# MINI_SSTC.net
KiCad netlist of a schematic drawn in EAGLE
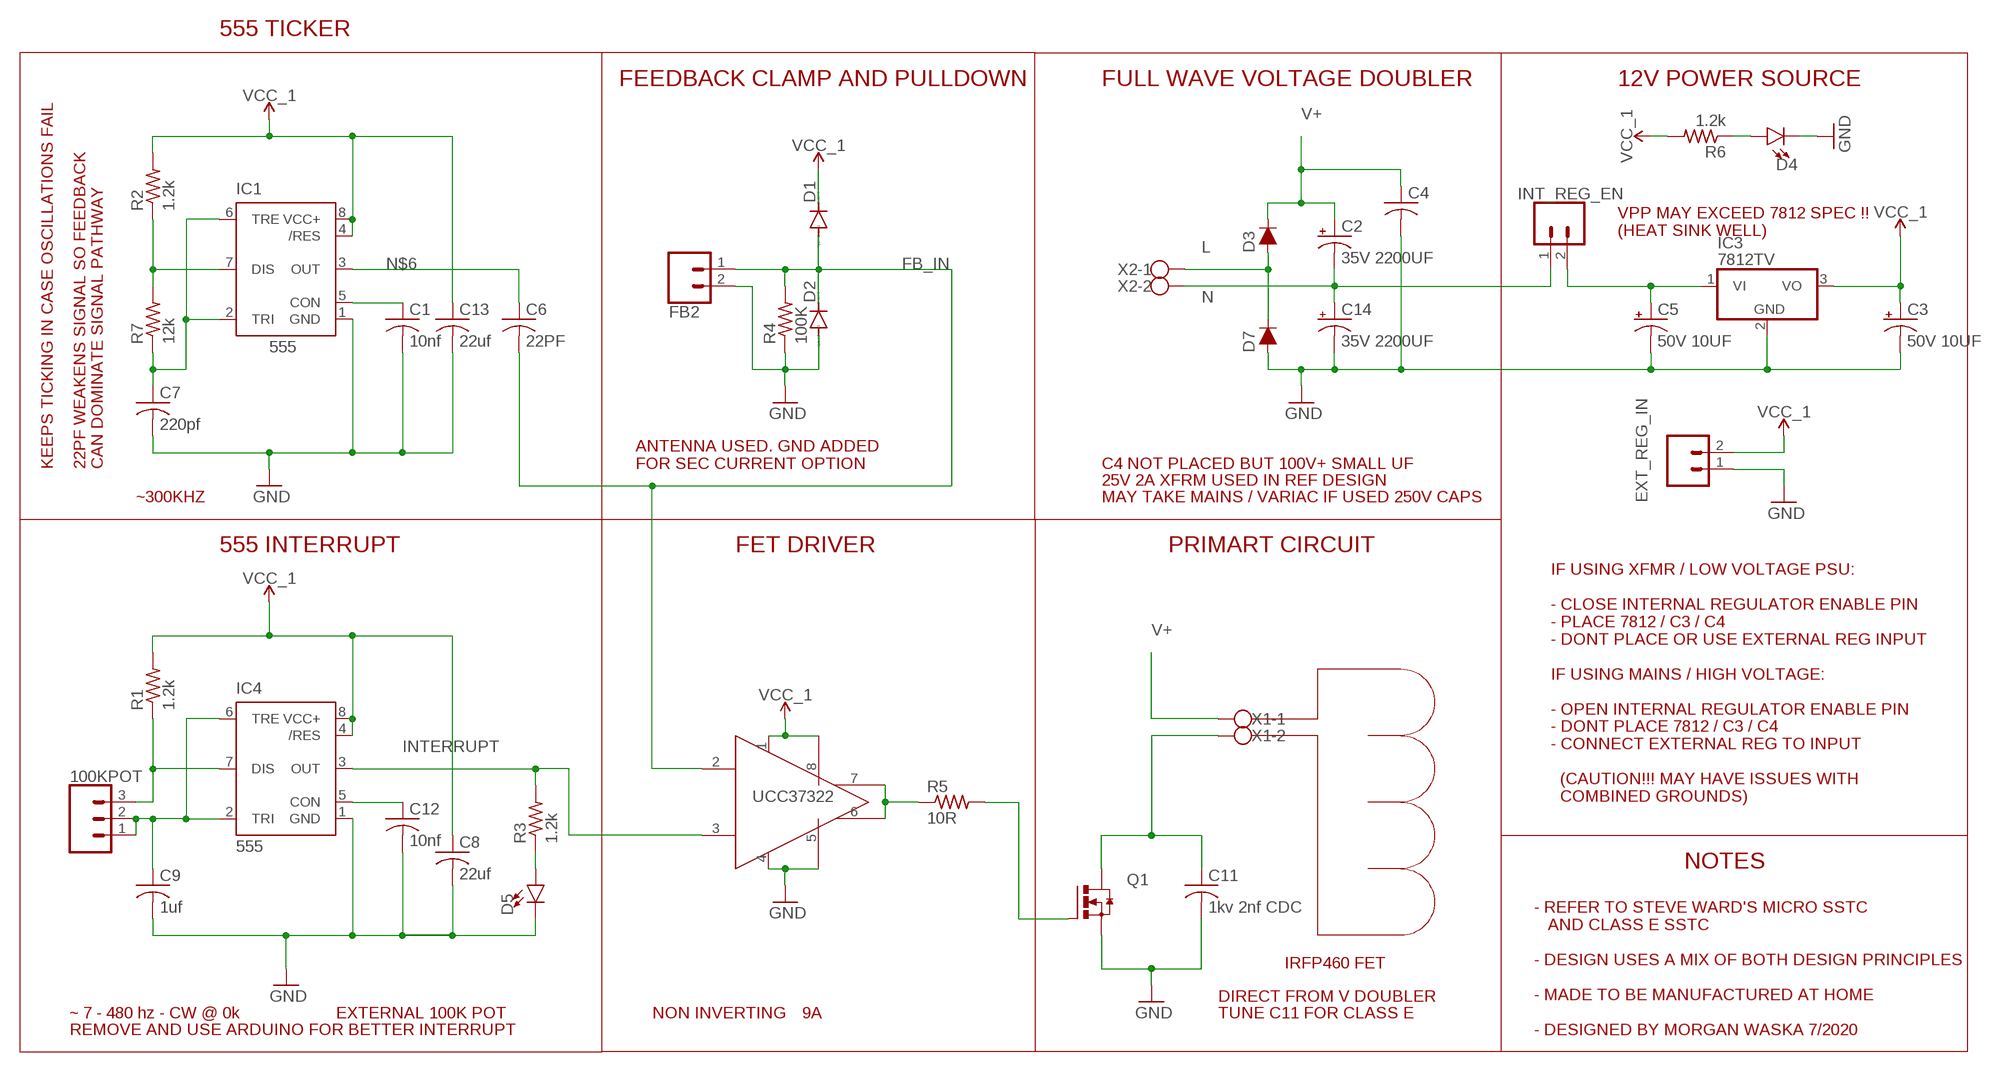
[diagram p0: schematic, sheet 1]

(export (version "E")
  (design (tool "Eeschema 10.0.6"))
  (components
    (comp (ref "100KPOT")
      (value "455-1750-1-ND")
      (footprint "eagle-import:1X03")
      (libsource (lib "eagle-import") (part "CONN_03"))
    )
    (comp (ref "C1")
      (value "10nf")
      (footprint "eagle-import:C025-040X050")
      (libsource (lib "eagle-import") (part "C-US025-040X050"))
    )
    (comp (ref "C2")
      (value "35V 2200UF")
      (footprint "eagle-import:E7,5-18")
      (libsource (lib "eagle-import") (part "CPOL-USE7.5-18"))
    )
    (comp (ref "C3")
      (value "50V 10UF")
      (footprint "eagle-import:E2,5-5")
      (libsource (lib "eagle-import") (part "CPOL-USE2.5-5"))
    )
    (comp (ref "C4")
      (value "C-US025-040X050")
      (footprint "eagle-import:C025-040X050")
      (libsource (lib "eagle-import") (part "C-US025-040X050"))
    )
    (comp (ref "C5")
      (value "50V 10UF")
      (footprint "eagle-import:E2,5-5")
      (libsource (lib "eagle-import") (part "CPOL-USE2.5-5"))
    )
    (comp (ref "C6")
      (value "22PF")
      (footprint "eagle-import:C025-040X050")
      (libsource (lib "eagle-import") (part "C-US025-040X050"))
    )
    (comp (ref "C7")
      (value "220pf")
      (footprint "eagle-import:C025-040X050")
      (libsource (lib "eagle-import") (part "C-US025-040X050"))
    )
    (comp (ref "C8")
      (value "22uf")
      (footprint "eagle-import:C025-040X050")
      (libsource (lib "eagle-import") (part "C-US025-040X050"))
    )
    (comp (ref "C9")
      (value "1uf")
      (footprint "eagle-import:C025-040X050")
      (libsource (lib "eagle-import") (part "C-US025-040X050"))
    )
    (comp (ref "C11")
      (value "1kv 2nf CDC")
      (footprint "eagle-import:C150-054X183")
      (libsource (lib "eagle-import") (part "C-US150-054X183"))
    )
    (comp (ref "C12")
      (value "10nf")
      (footprint "eagle-import:C025-040X050")
      (libsource (lib "eagle-import") (part "C-US025-040X050"))
    )
    (comp (ref "C13")
      (value "22uf")
      (footprint "eagle-import:C025-040X050")
      (libsource (lib "eagle-import") (part "C-US025-040X050"))
    )
    (comp (ref "C14")
      (value "35V 2200UF")
      (footprint "eagle-import:E7,5-18")
      (libsource (lib "eagle-import") (part "CPOL-USE7.5-18"))
    )
    (comp (ref "D1")
      (value "1N4148DO35-7")
      (footprint "eagle-import:DO35-7")
      (libsource (lib "eagle-import") (part "1N4148DO35-7"))
    )
    (comp (ref "D2")
      (value "1N4148DO35-7")
      (footprint "eagle-import:DO35-7")
      (libsource (lib "eagle-import") (part "1N4148DO35-7"))
    )
    (comp (ref "D3")
      (value "MUR460")
      (footprint "eagle-import:DIODE-1N4001-KIT")
      (libsource (lib "eagle-import") (part "DIODE-KIT2"))
    )
    (comp (ref "D4")
      (value "LED5MM")
      (footprint "eagle-import:LED_5MM")
      (libsource (lib "eagle-import") (part "LED5MM"))
    )
    (comp (ref "D5")
      (value "LED5MM")
      (footprint "eagle-import:LED_5MM")
      (libsource (lib "eagle-import") (part "LED5MM"))
    )
    (comp (ref "D7")
      (value "MUR460")
      (footprint "eagle-import:DIODE-1N4001-KIT")
      (libsource (lib "eagle-import") (part "DIODE-KIT2"))
    )
    (comp (ref "EXT_REG_IN")
      (value "CONN_02")
      (footprint "eagle-import:1X02")
      (libsource (lib "eagle-import") (part "CONN_02"))
    )
    (comp (ref "FB2")
      (value "CONN_02")
      (footprint "eagle-import:1X02")
      (libsource (lib "eagle-import") (part "CONN_02"))
    )
    (comp (ref "IC1")
      (value "555")
      (footprint "eagle-import:DIP08-KIT")
      (libsource (lib "eagle-import") (part "555KIT"))
    )
    (comp (ref "IC2")
      (value "UCC37322")
      (footprint "eagle-import:DIL08")
      (libsource (lib "eagle-import") (part "UCC37321DIL8"))
    )
    (comp (ref "IC3")
      (value "7812TV")
      (footprint "eagle-import:TO220V")
      (libsource (lib "eagle-import") (part "78TV12"))
    )
    (comp (ref "IC4")
      (value "555")
      (footprint "eagle-import:DIP08-KIT")
      (libsource (lib "eagle-import") (part "555KIT"))
    )
    (comp (ref "INT_REG_EN")
      (value "CONN_02")
      (footprint "eagle-import:1X02")
      (libsource (lib "eagle-import") (part "CONN_02"))
    )
    (comp (ref "Q1")
      (value "IRFP460")
      (footprint "eagle-import:TO247BV")
      (libsource (lib "eagle-import") (part "IRFP240"))
    )
    (comp (ref "R1")
      (value "1.2k")
      (footprint "eagle-import:0207_9")
      (libsource (lib "eagle-import") (part "R-US_0207/9"))
    )
    (comp (ref "R2")
      (value "1.2k")
      (footprint "eagle-import:0207_9")
      (libsource (lib "eagle-import") (part "R-US_0207/9"))
    )
    (comp (ref "R3")
      (value "1.2k")
      (footprint "eagle-import:0207_9")
      (libsource (lib "eagle-import") (part "R-US_0207/9"))
    )
    (comp (ref "R4")
      (value "100K")
      (footprint "eagle-import:0207_9")
      (libsource (lib "eagle-import") (part "R-US_0207/9"))
    )
    (comp (ref "R5")
      (value "10R")
      (footprint "eagle-import:0207_9")
      (libsource (lib "eagle-import") (part "R-US_0207/9"))
    )
    (comp (ref "R6")
      (value "1.2k")
      (footprint "eagle-import:0207_9")
      (libsource (lib "eagle-import") (part "R-US_0207/9"))
    )
    (comp (ref "R7")
      (value "12k")
      (footprint "eagle-import:0207_9")
      (libsource (lib "eagle-import") (part "R-US_0207/9"))
    )
    (comp (ref "X1")
      (value "W237-102")
      (footprint "eagle-import:W237-102")
      (fields (field (name "MPN") "237-102"))
      (libsource (lib "eagle-import") (part "W237-102"))
    )
    (comp (ref "X2")
      (value "W237-102")
      (footprint "eagle-import:W237-102")
      (fields (field (name "MPN") "237-102"))
      (libsource (lib "eagle-import") (part "W237-102"))
    )
  )
  (nets
    (net (code "1") (name "/FB_IN") (class "Default")
      (node (ref "C6") (pin "2") (pinfunction "2_2") (pintype "passive"))
      (node (ref "D1") (pin "A") (pinfunction "A_A") (pintype "passive"))
      (node (ref "D2") (pin "C") (pinfunction "C_C") (pintype "passive"))
      (node (ref "FB2") (pin "1") (pinfunction "1_1") (pintype "passive"))
      (node (ref "IC2") (pin "2") (pinfunction "2_IN_2") (pintype "input"))
      (node (ref "R4") (pin "2") (pinfunction "2_2") (pintype "passive"))
    )
    (net (code "2") (name "/INTERRUPT") (class "Default")
      (node (ref "IC2") (pin "3") (pinfunction "3_ENBL_3") (pintype "input"))
      (node (ref "IC4") (pin "3") (pinfunction "OUT_3") (pintype "output"))
      (node (ref "R3") (pin "2") (pinfunction "2_2") (pintype "passive"))
    )
    (net (code "3") (name "/L") (class "Default")
      (node (ref "D3") (pin "A") (pinfunction "A_A") (pintype "passive"))
      (node (ref "D7") (pin "C") (pinfunction "C_C") (pintype "passive"))
      (node (ref "X2") (pin "1") (pinfunction "KL_1") (pintype "passive"))
    )
    (net (code "4") (name "/N") (class "Default")
      (node (ref "C14") (pin "+") (pinfunction "+_+") (pintype "passive"))
      (node (ref "C2") (pin "-") (pinfunction "-_-") (pintype "passive"))
      (node (ref "INT_REG_EN") (pin "1") (pinfunction "1_1") (pintype "passive"))
      (node (ref "X2") (pin "2") (pinfunction "KL_2") (pintype "passive"))
    )
    (net (code "5") (name "/N$6") (class "Default")
      (node (ref "C6") (pin "1") (pinfunction "1_1") (pintype "passive"))
      (node (ref "IC1") (pin "3") (pinfunction "OUT_3") (pintype "output"))
    )
    (net (code "6") (name "/V+") (class "Default")
      (node (ref "C2") (pin "+") (pinfunction "+_+") (pintype "passive"))
      (node (ref "C4") (pin "1") (pinfunction "1_1") (pintype "passive"))
      (node (ref "D3") (pin "C") (pinfunction "C_C") (pintype "passive"))
      (node (ref "X1") (pin "1") (pinfunction "KL_1") (pintype "passive"))
    )
    (net (code "7") (name "GND") (class "Default")
      (node (ref "C1") (pin "2") (pinfunction "2_2") (pintype "passive"))
      (node (ref "C11") (pin "2") (pinfunction "2_2") (pintype "passive"))
      (node (ref "C12") (pin "2") (pinfunction "2_2") (pintype "passive"))
      (node (ref "C13") (pin "2") (pinfunction "2_2") (pintype "passive"))
      (node (ref "C14") (pin "-") (pinfunction "-_-") (pintype "passive"))
      (node (ref "C3") (pin "-") (pinfunction "-_-") (pintype "passive"))
      (node (ref "C4") (pin "2") (pinfunction "2_2") (pintype "passive"))
      (node (ref "C5") (pin "-") (pinfunction "-_-") (pintype "passive"))
      (node (ref "C7") (pin "2") (pinfunction "2_2") (pintype "passive"))
      (node (ref "C8") (pin "2") (pinfunction "2_2") (pintype "passive"))
      (node (ref "C9") (pin "2") (pinfunction "2_2") (pintype "passive"))
      (node (ref "D2") (pin "A") (pinfunction "A_A") (pintype "passive"))
      (node (ref "D4") (pin "K") (pinfunction "C_K") (pintype "passive"))
      (node (ref "D5") (pin "K") (pinfunction "C_K") (pintype "passive"))
      (node (ref "D7") (pin "A") (pinfunction "A_A") (pintype "passive"))
      (node (ref "EXT_REG_IN") (pin "1") (pinfunction "1_1") (pintype "passive"))
      (node (ref "FB2") (pin "2") (pinfunction "2_2") (pintype "passive"))
      (node (ref "IC1") (pin "1") (pinfunction "GND_1") (pintype "power_in"))
      (node (ref "IC2") (pin "4") (pinfunction "4_AGND_4") (pintype "power_in"))
      (node (ref "IC2") (pin "5") (pinfunction "5_PGND_5") (pintype "power_in"))
      (node (ref "IC3") (pin "2") (pinfunction "GND_2") (pintype "passive"))
      (node (ref "IC4") (pin "1") (pinfunction "GND_1") (pintype "power_in"))
      (node (ref "Q1") (pin "S") (pinfunction "S_S") (pintype "passive"))
      (node (ref "R4") (pin "1") (pinfunction "1_1") (pintype "passive"))
    )
    (net (code "8") (name "Net-(D4-PadA)") (class "Default")
      (node (ref "D4") (pin "A") (pinfunction "A_A") (pintype "passive"))
      (node (ref "R6") (pin "1") (pinfunction "1_1") (pintype "passive"))
    )
    (net (code "9") (name "Net-(D5-PadA)") (class "Default")
      (node (ref "D5") (pin "A") (pinfunction "A_A") (pintype "passive"))
      (node (ref "R3") (pin "1") (pinfunction "1_1") (pintype "passive"))
    )
    (net (code "10") (name "Net-(IC1-CON)") (class "Default")
      (node (ref "C1") (pin "1") (pinfunction "1_1") (pintype "passive"))
      (node (ref "IC1") (pin "5") (pinfunction "CON_5") (pintype "input"))
    )
    (net (code "11") (name "Net-(IC1-DIS)") (class "Default")
      (node (ref "IC1") (pin "7") (pinfunction "DIS_7") (pintype "input"))
      (node (ref "R2") (pin "1") (pinfunction "1_1") (pintype "passive"))
      (node (ref "R7") (pin "2") (pinfunction "2_2") (pintype "passive"))
    )
    (net (code "12") (name "Net-(IC1-TRE)") (class "Default")
      (node (ref "C7") (pin "1") (pinfunction "1_1") (pintype "passive"))
      (node (ref "IC1") (pin "2") (pinfunction "TRI_2") (pintype "input"))
      (node (ref "IC1") (pin "6") (pinfunction "TRE_6") (pintype "input"))
      (node (ref "R7") (pin "1") (pinfunction "1_1") (pintype "passive"))
    )
    (net (code "13") (name "Net-(IC2-6_OUT)") (class "Default")
      (node (ref "IC2") (pin "6") (pinfunction "6_OUT_6") (pintype "output"))
      (node (ref "IC2") (pin "7") (pinfunction "7_OUT_7") (pintype "output"))
      (node (ref "R5") (pin "1") (pinfunction "1_1") (pintype "passive"))
    )
    (net (code "14") (name "Net-(IC3-VI)") (class "Default")
      (node (ref "C5") (pin "+") (pinfunction "+_+") (pintype "passive"))
      (node (ref "IC3") (pin "1") (pinfunction "VI_1") (pintype "input"))
      (node (ref "INT_REG_EN") (pin "2") (pinfunction "2_2") (pintype "passive"))
    )
    (net (code "15") (name "Net-(IC4-CON)") (class "Default")
      (node (ref "C12") (pin "1") (pinfunction "1_1") (pintype "passive"))
      (node (ref "IC4") (pin "5") (pinfunction "CON_5") (pintype "input"))
    )
    (net (code "16") (name "Net-(IC4-DIS)") (class "Default")
      (node (ref "100KPOT") (pin "3") (pinfunction "3_3") (pintype "passive"))
      (node (ref "IC4") (pin "7") (pinfunction "DIS_7") (pintype "input"))
      (node (ref "R1") (pin "1") (pinfunction "1_1") (pintype "passive"))
    )
    (net (code "17") (name "Net-(IC4-TRE)") (class "Default")
      (node (ref "100KPOT") (pin "1") (pinfunction "1_1") (pintype "passive"))
      (node (ref "100KPOT") (pin "2") (pinfunction "2_2") (pintype "passive"))
      (node (ref "C9") (pin "1") (pinfunction "1_1") (pintype "passive"))
      (node (ref "IC4") (pin "2") (pinfunction "TRI_2") (pintype "input"))
      (node (ref "IC4") (pin "6") (pinfunction "TRE_6") (pintype "input"))
    )
    (net (code "18") (name "Net-(Q1-PadG)") (class "Default")
      (node (ref "Q1") (pin "G") (pinfunction "G_G") (pintype "passive"))
      (node (ref "R5") (pin "2") (pinfunction "2_2") (pintype "passive"))
    )
    (net (code "19") (name "Net-(X1B-KL)") (class "Default")
      (node (ref "C11") (pin "1") (pinfunction "1_1") (pintype "passive"))
      (node (ref "Q1") (pin "D") (pinfunction "D_D") (pintype "passive"))
      (node (ref "X1") (pin "2") (pinfunction "KL_2") (pintype "passive"))
    )
    (net (code "20") (name "VCC_1") (class "Default")
      (node (ref "C13") (pin "1") (pinfunction "1_1") (pintype "passive"))
      (node (ref "C3") (pin "+") (pinfunction "+_+") (pintype "passive"))
      (node (ref "C8") (pin "1") (pinfunction "1_1") (pintype "passive"))
      (node (ref "D1") (pin "C") (pinfunction "C_C") (pintype "passive"))
      (node (ref "EXT_REG_IN") (pin "2") (pinfunction "2_2") (pintype "passive"))
      (node (ref "IC1") (pin "4") (pinfunction "/RES_4") (pintype "input"))
      (node (ref "IC1") (pin "8") (pinfunction "VCC+_8") (pintype "power_in"))
      (node (ref "IC2") (pin "1") (pinfunction "1_VDD_1") (pintype "power_in"))
      (node (ref "IC2") (pin "8") (pinfunction "8_VDD_8") (pintype "power_in"))
      (node (ref "IC3") (pin "3") (pinfunction "VO_3") (pintype "passive"))
      (node (ref "IC4") (pin "4") (pinfunction "/RES_4") (pintype "input"))
      (node (ref "IC4") (pin "8") (pinfunction "VCC+_8") (pintype "power_in"))
      (node (ref "R1") (pin "2") (pinfunction "2_2") (pintype "passive"))
      (node (ref "R2") (pin "2") (pinfunction "2_2") (pintype "passive"))
      (node (ref "R6") (pin "2") (pinfunction "2_2") (pintype "passive"))
    )
  )
)
